# mainboard.net
KiCad netlist of a schematic drawn in EAGLE
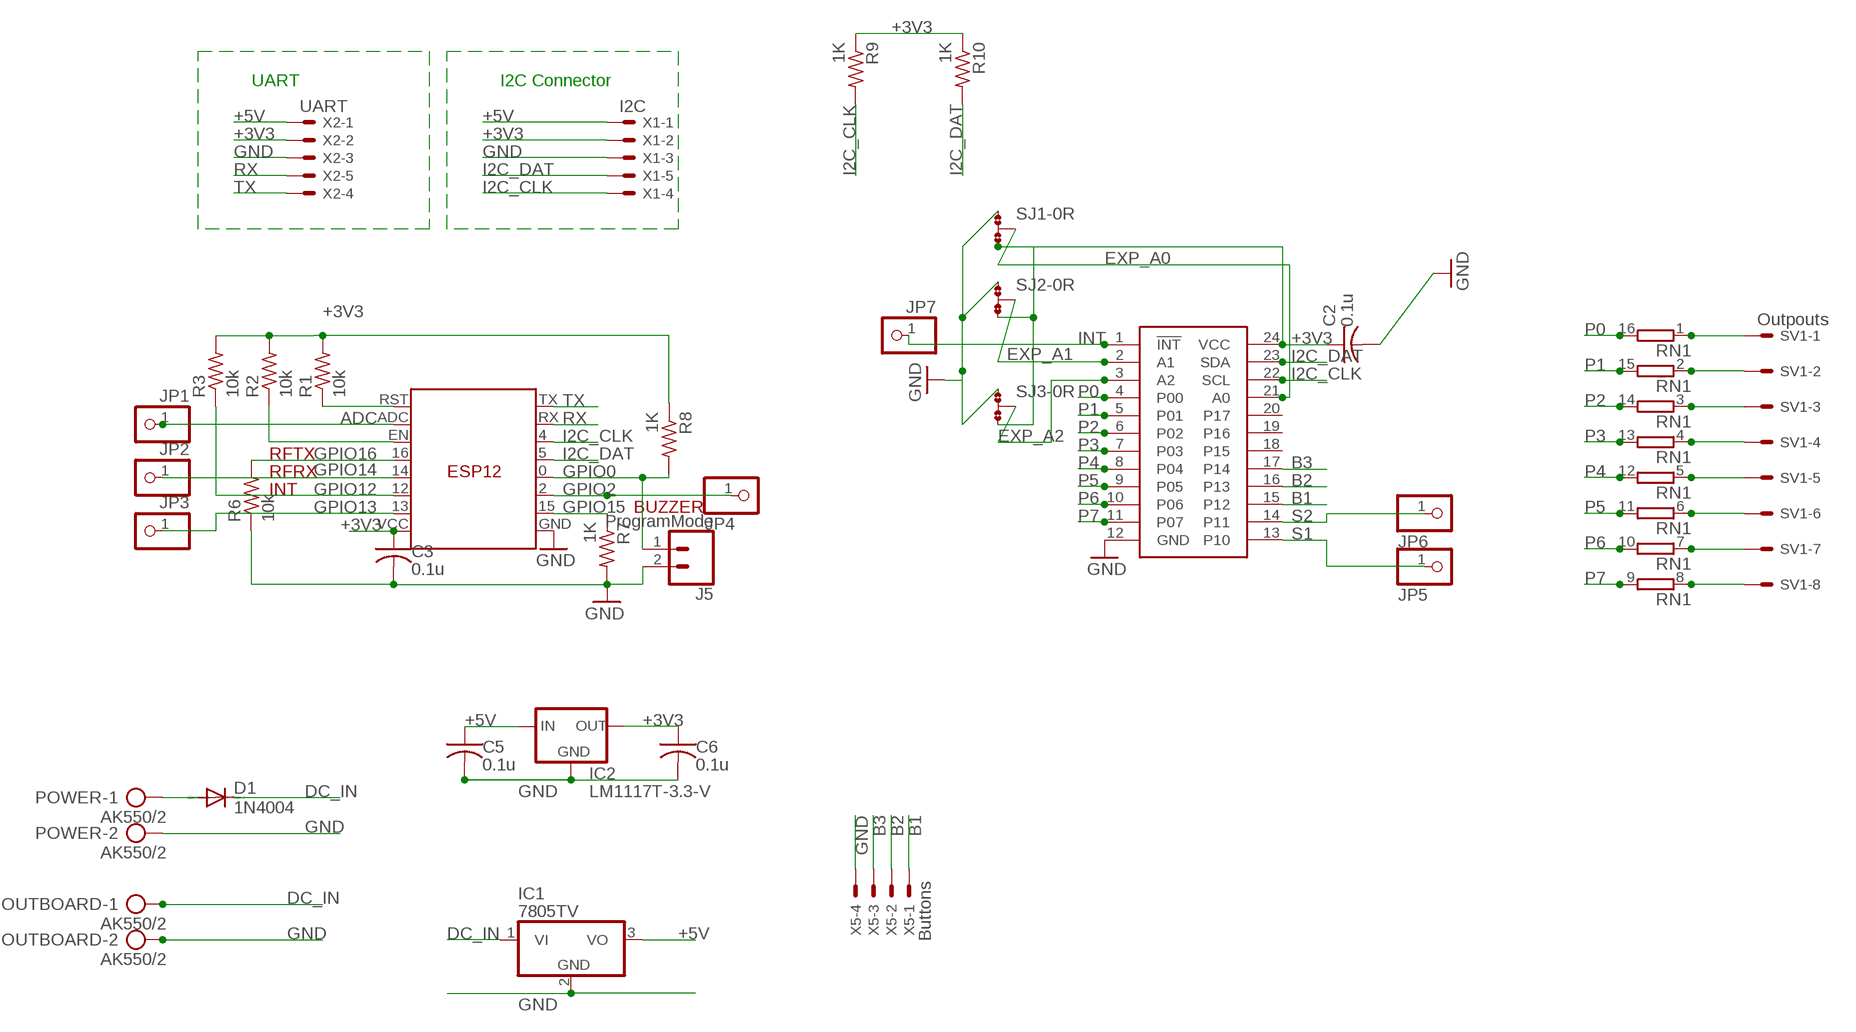
[diagram p0: schematic, sheet 1]

(export (version "E")
  (design (tool "Eeschema 10.0.6"))
  (components
    (comp (ref "C2")
      (value "0.1u")
      (footprint "eagle-import:C050-045X075")
      (libsource (lib "eagle-import") (part "C-US050-045X075"))
    )
    (comp (ref "C3")
      (value "0.1u")
      (footprint "eagle-import:C050-045X075")
      (libsource (lib "eagle-import") (part "C-US050-045X075"))
    )
    (comp (ref "C5")
      (value "0.1u")
      (footprint "eagle-import:C050-045X075")
      (libsource (lib "eagle-import") (part "C-US050-045X075"))
    )
    (comp (ref "C6")
      (value "0.1u")
      (footprint "eagle-import:C050-045X075")
      (libsource (lib "eagle-import") (part "C-US050-045X075"))
    )
    (comp (ref "D1")
      (value "1N4004")
      (footprint "eagle-import:DO41-10")
      (libsource (lib "eagle-import") (part "1N4004"))
    )
    (comp (ref "ESP")
      (value "ESP-12N")
      (footprint "eagle-import:ESP12_WES")
      (libsource (lib "eagle-import") (part "ESP12ESPWES"))
    )
    (comp (ref "IC1")
      (value "7805TV")
      (footprint "eagle-import:TO220V")
      (libsource (lib "eagle-import") (part "78TV05"))
    )
    (comp (ref "IC2")
      (value "LM1117T-3.3-V")
      (footprint "eagle-import:TO220V")
      (libsource (lib "eagle-import") (part "LM1117T--V3.3"))
    )
    (comp (ref "J5")
      (value "ProgramMode")
      (footprint "eagle-import:1X02")
      (libsource (lib "eagle-import") (part "CONN_02"))
    )
    (comp (ref "JP1")
      (value "PINHD-1X1")
      (footprint "eagle-import:1X01")
      (libsource (lib "eagle-import") (part "PINHD-1X1"))
    )
    (comp (ref "JP2")
      (value "PINHD-1X1")
      (footprint "eagle-import:1X01")
      (libsource (lib "eagle-import") (part "PINHD-1X1"))
    )
    (comp (ref "JP3")
      (value "PINHD-1X1")
      (footprint "eagle-import:1X01")
      (libsource (lib "eagle-import") (part "PINHD-1X1"))
    )
    (comp (ref "JP4")
      (value "PINHD-1X1")
      (footprint "eagle-import:1X01")
      (libsource (lib "eagle-import") (part "PINHD-1X1"))
    )
    (comp (ref "JP5")
      (value "PINHD-1X1")
      (footprint "eagle-import:1X01")
      (libsource (lib "eagle-import") (part "PINHD-1X1"))
    )
    (comp (ref "JP6")
      (value "PINHD-1X1")
      (footprint "eagle-import:1X01")
      (libsource (lib "eagle-import") (part "PINHD-1X1"))
    )
    (comp (ref "JP7")
      (value "PINHD-1X1")
      (footprint "eagle-import:1X01")
      (libsource (lib "eagle-import") (part "PINHD-1X1"))
    )
    (comp (ref "OUTBOARD")
      (value "AK550/2")
      (footprint "eagle-import:AK550_2")
      (libsource (lib "eagle-import") (part "AK550/2"))
    )
    (comp (ref "PCA9555")
      (value "PCA9555")
      (footprint "eagle-import:TSSOP24")
      (libsource (lib "eagle-import") (part "PCF8575TSSOP24"))
    )
    (comp (ref "POWER")
      (value "AK550/2")
      (footprint "eagle-import:AK550_2")
      (libsource (lib "eagle-import") (part "AK550/2"))
    )
    (comp (ref "R1")
      (value "10k")
      (footprint "eagle-import:0204_7")
      (libsource (lib "eagle-import") (part "R-US_0204/7"))
    )
    (comp (ref "R2")
      (value "10k")
      (footprint "eagle-import:0204_5")
      (libsource (lib "eagle-import") (part "R-US_0204/5"))
    )
    (comp (ref "R3")
      (value "10k")
      (footprint "eagle-import:0204_7")
      (libsource (lib "eagle-import") (part "R-US_0204/7"))
    )
    (comp (ref "R6")
      (value "10k")
      (footprint "eagle-import:0204_7")
      (libsource (lib "eagle-import") (part "R-US_0204/7"))
    )
    (comp (ref "R7")
      (value "1K")
      (footprint "eagle-import:0204_7")
      (libsource (lib "eagle-import") (part "R-US_0204/7"))
    )
    (comp (ref "R8")
      (value "1K")
      (footprint "eagle-import:0204_7")
      (libsource (lib "eagle-import") (part "R-US_0204/7"))
    )
    (comp (ref "R9")
      (value "1K")
      (footprint "eagle-import:0204_7")
      (libsource (lib "eagle-import") (part "R-US_0204/7"))
    )
    (comp (ref "R10")
      (value "1K")
      (footprint "eagle-import:0204_7")
      (libsource (lib "eagle-import") (part "R-US_0204/7"))
    )
    (comp (ref "RN1")
      (value "8R-P")
      (footprint "eagle-import:DIL16")
      (libsource (lib "eagle-import") (part "8R-P"))
    )
    (comp (ref "SJ1")
      (value "0R-JUMPA")
      (footprint "eagle-import:A0R-JMP")
      (libsource (lib "eagle-import") (part "0R-JUMPA"))
    )
    (comp (ref "SJ2")
      (value "0R-JUMPA")
      (footprint "eagle-import:A0R-JMP")
      (libsource (lib "eagle-import") (part "0R-JUMPA"))
    )
    (comp (ref "SJ3")
      (value "0R-JUMPA")
      (footprint "eagle-import:A0R-JMP")
      (libsource (lib "eagle-import") (part "0R-JUMPA"))
    )
    (comp (ref "SV1")
      (value "Outpouts")
      (footprint "eagle-import:22-23-2081")
      (fields (field (name "MF") "MOLEX") (field (name "MPN") "22-23-2081"))
      (libsource (lib "eagle-import") (part "22-23-2081"))
    )
    (comp (ref "X1")
      (value "I2C")
      (footprint "eagle-import:22-23-2051")
      (fields (field (name "MF") "MOLEX") (field (name "MPN") "22-23-2051"))
      (libsource (lib "eagle-import") (part "22-23-2051"))
    )
    (comp (ref "X2")
      (value "UART")
      (footprint "eagle-import:22-23-2051")
      (fields (field (name "MF") "MOLEX") (field (name "MPN") "22-23-2051"))
      (libsource (lib "eagle-import") (part "22-23-2051"))
    )
    (comp (ref "X5")
      (value "Buttons")
      (footprint "eagle-import:22-23-2041")
      (fields (field (name "MF") "MOLEX") (field (name "MPN") "22-23-2041"))
      (libsource (lib "eagle-import") (part "22-23-2041"))
    )
  )
  (nets
    (net (code "1") (name "/+3V3") (class "Default")
      (node (ref "C2") (pin "1") (pinfunction "1_1") (pintype "passive"))
      (node (ref "C3") (pin "1") (pinfunction "1_1") (pintype "passive"))
      (node (ref "C6") (pin "1") (pinfunction "1_1") (pintype "passive"))
      (node (ref "ESP") (pin "VCC") (pinfunction "VCC_VCC") (pintype "power_in"))
      (node (ref "IC2") (pin "2") (pinfunction "OUT_2") (pintype "passive"))
      (node (ref "PCA9555") (pin "24") (pinfunction "VCC_24") (pintype "power_in"))
      (node (ref "R1") (pin "2") (pinfunction "2_2") (pintype "passive"))
      (node (ref "R10") (pin "1") (pinfunction "1_1") (pintype "passive"))
      (node (ref "R2") (pin "2") (pinfunction "2_2") (pintype "passive"))
      (node (ref "R3") (pin "2") (pinfunction "2_2") (pintype "passive"))
      (node (ref "R8") (pin "1") (pinfunction "1_1") (pintype "passive"))
      (node (ref "R9") (pin "1") (pinfunction "1_1") (pintype "passive"))
      (node (ref "SJ1") (pin "3") (pinfunction "3_3") (pintype "passive"))
      (node (ref "SJ2") (pin "3") (pinfunction "3_3") (pintype "passive"))
      (node (ref "SJ3") (pin "3") (pinfunction "3_3") (pintype "passive"))
      (node (ref "X1") (pin "2") (pinfunction "S_2") (pintype "passive"))
      (node (ref "X2") (pin "2") (pinfunction "S_2") (pintype "passive"))
    )
    (net (code "2") (name "/+5V") (class "Default")
      (node (ref "C5") (pin "1") (pinfunction "1_1") (pintype "passive"))
      (node (ref "IC1") (pin "3") (pinfunction "VO_3") (pintype "passive"))
      (node (ref "IC2") (pin "3") (pinfunction "IN_3") (pintype "input"))
      (node (ref "X1") (pin "1") (pinfunction "S_1") (pintype "passive"))
      (node (ref "X2") (pin "1") (pinfunction "S_1") (pintype "passive"))
    )
    (net (code "3") (name "/ADC") (class "Default")
      (node (ref "ESP") (pin "ADC") (pinfunction "ADC_ADC") (pintype "bidirectional"))
      (node (ref "JP1") (pin "1") (pinfunction "1_1") (pintype "passive"))
    )
    (net (code "4") (name "/B1") (class "Default")
      (node (ref "PCA9555") (pin "15") (pinfunction "P12_15") (pintype "bidirectional"))
      (node (ref "X5") (pin "1") (pinfunction "S_1") (pintype "passive"))
    )
    (net (code "5") (name "/B2") (class "Default")
      (node (ref "PCA9555") (pin "16") (pinfunction "P13_16") (pintype "bidirectional"))
      (node (ref "X5") (pin "2") (pinfunction "S_2") (pintype "passive"))
    )
    (net (code "6") (name "/B3") (class "Default")
      (node (ref "PCA9555") (pin "17") (pinfunction "P14_17") (pintype "bidirectional"))
      (node (ref "X5") (pin "3") (pinfunction "S_3") (pintype "passive"))
    )
    (net (code "7") (name "/DC_IN") (class "Default")
      (node (ref "D1") (pin "C") (pinfunction "C_C") (pintype "passive"))
      (node (ref "IC1") (pin "1") (pinfunction "VI_1") (pintype "input"))
      (node (ref "OUTBOARD") (pin "1") (pinfunction "KL_1") (pintype "passive"))
    )
    (net (code "8") (name "/EXP_A0") (class "Default")
      (node (ref "PCA9555") (pin "21") (pinfunction "A0_21") (pintype "bidirectional"))
      (node (ref "SJ1") (pin "2") (pinfunction "2_2") (pintype "passive"))
    )
    (net (code "9") (name "/EXP_A1") (class "Default")
      (node (ref "PCA9555") (pin "2") (pinfunction "A1_2") (pintype "bidirectional"))
      (node (ref "SJ2") (pin "2") (pinfunction "2_2") (pintype "passive"))
    )
    (net (code "10") (name "/EXP_A2") (class "Default")
      (node (ref "PCA9555") (pin "3") (pinfunction "A2_3") (pintype "bidirectional"))
      (node (ref "SJ3") (pin "2") (pinfunction "2_2") (pintype "passive"))
    )
    (net (code "11") (name "/GPIO0") (class "Default")
      (node (ref "ESP") (pin "0") (pinfunction "G0_0") (pintype "bidirectional"))
      (node (ref "J5") (pin "1") (pinfunction "1_1") (pintype "passive"))
      (node (ref "R8") (pin "2") (pinfunction "2_2") (pintype "passive"))
    )
    (net (code "12") (name "/GPIO2") (class "Default")
      (node (ref "ESP") (pin "2") (pinfunction "G2_2") (pintype "bidirectional"))
      (node (ref "JP4") (pin "1") (pinfunction "1_1") (pintype "passive"))
    )
    (net (code "13") (name "/GPIO12") (class "Default")
      (node (ref "ESP") (pin "12") (pinfunction "G12_12") (pintype "bidirectional"))
      (node (ref "R3") (pin "1") (pinfunction "1_1") (pintype "passive"))
    )
    (net (code "14") (name "/GPIO13") (class "Default")
      (node (ref "ESP") (pin "13") (pinfunction "G13_13") (pintype "bidirectional"))
      (node (ref "JP3") (pin "1") (pinfunction "1_1") (pintype "passive"))
    )
    (net (code "15") (name "/GPIO14") (class "Default")
      (node (ref "ESP") (pin "14") (pinfunction "G14_14") (pintype "bidirectional"))
      (node (ref "JP2") (pin "1") (pinfunction "1_1") (pintype "passive"))
    )
    (net (code "16") (name "/GPIO15") (class "Default")
      (node (ref "ESP") (pin "15") (pinfunction "G15_15") (pintype "bidirectional"))
      (node (ref "R7") (pin "1") (pinfunction "1_1") (pintype "passive"))
    )
    (net (code "17") (name "/GPIO16") (class "Default")
      (node (ref "ESP") (pin "16") (pinfunction "G16_16") (pintype "bidirectional"))
      (node (ref "R6") (pin "2") (pinfunction "2_2") (pintype "passive"))
    )
    (net (code "18") (name "/I2C_CLK") (class "Default")
      (node (ref "ESP") (pin "4") (pinfunction "G4_4") (pintype "bidirectional"))
      (node (ref "PCA9555") (pin "22") (pinfunction "SCL_22") (pintype "bidirectional"))
      (node (ref "R9") (pin "2") (pinfunction "2_2") (pintype "passive"))
      (node (ref "X1") (pin "4") (pinfunction "S_4") (pintype "passive"))
    )
    (net (code "19") (name "/I2C_DAT") (class "Default")
      (node (ref "ESP") (pin "5") (pinfunction "G5_5") (pintype "bidirectional"))
      (node (ref "PCA9555") (pin "23") (pinfunction "SDA_23") (pintype "bidirectional"))
      (node (ref "R10") (pin "2") (pinfunction "2_2") (pintype "passive"))
      (node (ref "X1") (pin "5") (pinfunction "S_5") (pintype "passive"))
    )
    (net (code "20") (name "/INT") (class "Default")
      (node (ref "JP7") (pin "1") (pinfunction "1_1") (pintype "passive"))
      (node (ref "PCA9555") (pin "1") (pinfunction "~{INT}_1") (pintype "bidirectional"))
    )
    (net (code "21") (name "/P0") (class "Default")
      (node (ref "PCA9555") (pin "4") (pinfunction "P00_4") (pintype "bidirectional"))
      (node (ref "RN1") (pin "16") (pinfunction "2_16") (pintype "passive"))
    )
    (net (code "22") (name "/P1") (class "Default")
      (node (ref "PCA9555") (pin "5") (pinfunction "P01_5") (pintype "bidirectional"))
      (node (ref "RN1") (pin "15") (pinfunction "2_15") (pintype "passive"))
    )
    (net (code "23") (name "/P2") (class "Default")
      (node (ref "PCA9555") (pin "6") (pinfunction "P02_6") (pintype "bidirectional"))
      (node (ref "RN1") (pin "14") (pinfunction "2_14") (pintype "passive"))
    )
    (net (code "24") (name "/P3") (class "Default")
      (node (ref "PCA9555") (pin "7") (pinfunction "P03_7") (pintype "bidirectional"))
      (node (ref "RN1") (pin "13") (pinfunction "2_13") (pintype "passive"))
    )
    (net (code "25") (name "/P4") (class "Default")
      (node (ref "PCA9555") (pin "8") (pinfunction "P04_8") (pintype "bidirectional"))
      (node (ref "RN1") (pin "12") (pinfunction "2_12") (pintype "passive"))
    )
    (net (code "26") (name "/P5") (class "Default")
      (node (ref "PCA9555") (pin "9") (pinfunction "P05_9") (pintype "bidirectional"))
      (node (ref "RN1") (pin "11") (pinfunction "2_11") (pintype "passive"))
    )
    (net (code "27") (name "/P6") (class "Default")
      (node (ref "PCA9555") (pin "10") (pinfunction "P06_10") (pintype "bidirectional"))
      (node (ref "RN1") (pin "10") (pinfunction "2_10") (pintype "passive"))
    )
    (net (code "28") (name "/P7") (class "Default")
      (node (ref "PCA9555") (pin "11") (pinfunction "P07_11") (pintype "bidirectional"))
      (node (ref "RN1") (pin "9") (pinfunction "2_9") (pintype "passive"))
    )
    (net (code "29") (name "/RX") (class "Default")
      (node (ref "ESP") (pin "RX") (pinfunction "RX_RX") (pintype "bidirectional"))
      (node (ref "X2") (pin "5") (pinfunction "S_5") (pintype "passive"))
    )
    (net (code "30") (name "/S1") (class "Default")
      (node (ref "JP5") (pin "1") (pinfunction "1_1") (pintype "passive"))
      (node (ref "PCA9555") (pin "13") (pinfunction "P10_13") (pintype "bidirectional"))
    )
    (net (code "31") (name "/S2") (class "Default")
      (node (ref "JP6") (pin "1") (pinfunction "1_1") (pintype "passive"))
      (node (ref "PCA9555") (pin "14") (pinfunction "P11_14") (pintype "bidirectional"))
    )
    (net (code "32") (name "/TX") (class "Default")
      (node (ref "ESP") (pin "TX") (pinfunction "TX_TX") (pintype "bidirectional"))
      (node (ref "X2") (pin "4") (pinfunction "S_4") (pintype "passive"))
    )
    (net (code "33") (name "GND") (class "Default")
      (node (ref "C2") (pin "2") (pinfunction "2_2") (pintype "passive"))
      (node (ref "C3") (pin "2") (pinfunction "2_2") (pintype "passive"))
      (node (ref "C5") (pin "2") (pinfunction "2_2") (pintype "passive"))
      (node (ref "C6") (pin "2") (pinfunction "2_2") (pintype "passive"))
      (node (ref "ESP") (pin "GND") (pinfunction "GND_GND") (pintype "power_in"))
      (node (ref "IC1") (pin "2") (pinfunction "GND_2") (pintype "passive"))
      (node (ref "IC2") (pin "1") (pinfunction "GND_1") (pintype "input"))
      (node (ref "J5") (pin "2") (pinfunction "2_2") (pintype "passive"))
      (node (ref "OUTBOARD") (pin "2") (pinfunction "KL_2") (pintype "passive"))
      (node (ref "PCA9555") (pin "12") (pinfunction "GND_12") (pintype "power_in"))
      (node (ref "POWER") (pin "2") (pinfunction "KL_2") (pintype "passive"))
      (node (ref "R6") (pin "1") (pinfunction "1_1") (pintype "passive"))
      (node (ref "R7") (pin "2") (pinfunction "2_2") (pintype "passive"))
      (node (ref "SJ1") (pin "1") (pinfunction "1_1") (pintype "passive"))
      (node (ref "SJ2") (pin "1") (pinfunction "1_1") (pintype "passive"))
      (node (ref "SJ3") (pin "1") (pinfunction "1_1") (pintype "passive"))
      (node (ref "X1") (pin "3") (pinfunction "S_3") (pintype "passive"))
      (node (ref "X2") (pin "3") (pinfunction "S_3") (pintype "passive"))
      (node (ref "X5") (pin "4") (pinfunction "S_4") (pintype "passive"))
    )
    (net (code "34") (name "Net-(ESP-PadEN)") (class "Default")
      (node (ref "ESP") (pin "EN") (pinfunction "EN_EN") (pintype "bidirectional"))
      (node (ref "R2") (pin "1") (pinfunction "1_1") (pintype "passive"))
    )
    (net (code "35") (name "Net-(ESP-PadRST)") (class "Default")
      (node (ref "ESP") (pin "RST") (pinfunction "RST_RST") (pintype "bidirectional"))
      (node (ref "R1") (pin "1") (pinfunction "1_1") (pintype "passive"))
    )
    (net (code "36") (name "Net-(POWERA-KL)") (class "Default")
      (node (ref "D1") (pin "A") (pinfunction "A_A") (pintype "passive"))
      (node (ref "POWER") (pin "1") (pinfunction "KL_1") (pintype "passive"))
    )
    (net (code "37") (name "Net-(RN1B-1)") (class "Default")
      (node (ref "RN1") (pin "2") (pinfunction "1_2") (pintype "passive"))
      (node (ref "SV1") (pin "2") (pinfunction "S_2") (pintype "passive"))
    )
    (net (code "38") (name "Net-(RN1C-1)") (class "Default")
      (node (ref "RN1") (pin "3") (pinfunction "1_3") (pintype "passive"))
      (node (ref "SV1") (pin "3") (pinfunction "S_3") (pintype "passive"))
    )
    (net (code "39") (name "Net-(RN1D-1)") (class "Default")
      (node (ref "RN1") (pin "4") (pinfunction "1_4") (pintype "passive"))
      (node (ref "SV1") (pin "4") (pinfunction "S_4") (pintype "passive"))
    )
    (net (code "40") (name "Net-(RN1E-1)") (class "Default")
      (node (ref "RN1") (pin "5") (pinfunction "1_5") (pintype "passive"))
      (node (ref "SV1") (pin "5") (pinfunction "S_5") (pintype "passive"))
    )
    (net (code "41") (name "Net-(RN1F-1)") (class "Default")
      (node (ref "RN1") (pin "6") (pinfunction "1_6") (pintype "passive"))
      (node (ref "SV1") (pin "6") (pinfunction "S_6") (pintype "passive"))
    )
    (net (code "42") (name "Net-(RN1G-1)") (class "Default")
      (node (ref "RN1") (pin "7") (pinfunction "1_7") (pintype "passive"))
      (node (ref "SV1") (pin "7") (pinfunction "S_7") (pintype "passive"))
    )
    (net (code "43") (name "Net-(RN1H-1)") (class "Default")
      (node (ref "RN1") (pin "8") (pinfunction "1_8") (pintype "passive"))
      (node (ref "SV1") (pin "8") (pinfunction "S_8") (pintype "passive"))
    )
    (net (code "44") (name "Net-(SV1A-S)") (class "Default")
      (node (ref "RN1") (pin "1") (pinfunction "1_1") (pintype "passive"))
      (node (ref "SV1") (pin "1") (pinfunction "S_1") (pintype "passive"))
    )
    (net (code "45") (name "unconnected-(PCA9555-P15-Pad18)") (class "Default")
      (node (ref "PCA9555") (pin "18") (pinfunction "P15_18") (pintype "bidirectional"))
    )
    (net (code "46") (name "unconnected-(PCA9555-P16-Pad19)") (class "Default")
      (node (ref "PCA9555") (pin "19") (pinfunction "P16_19") (pintype "bidirectional"))
    )
    (net (code "47") (name "unconnected-(PCA9555-P17-Pad20)") (class "Default")
      (node (ref "PCA9555") (pin "20") (pinfunction "P17_20") (pintype "bidirectional"))
    )
  )
)
